# RcMPPT-BMS-Interface.net
KiCad netlist of a schematic drawn in Altium Designer
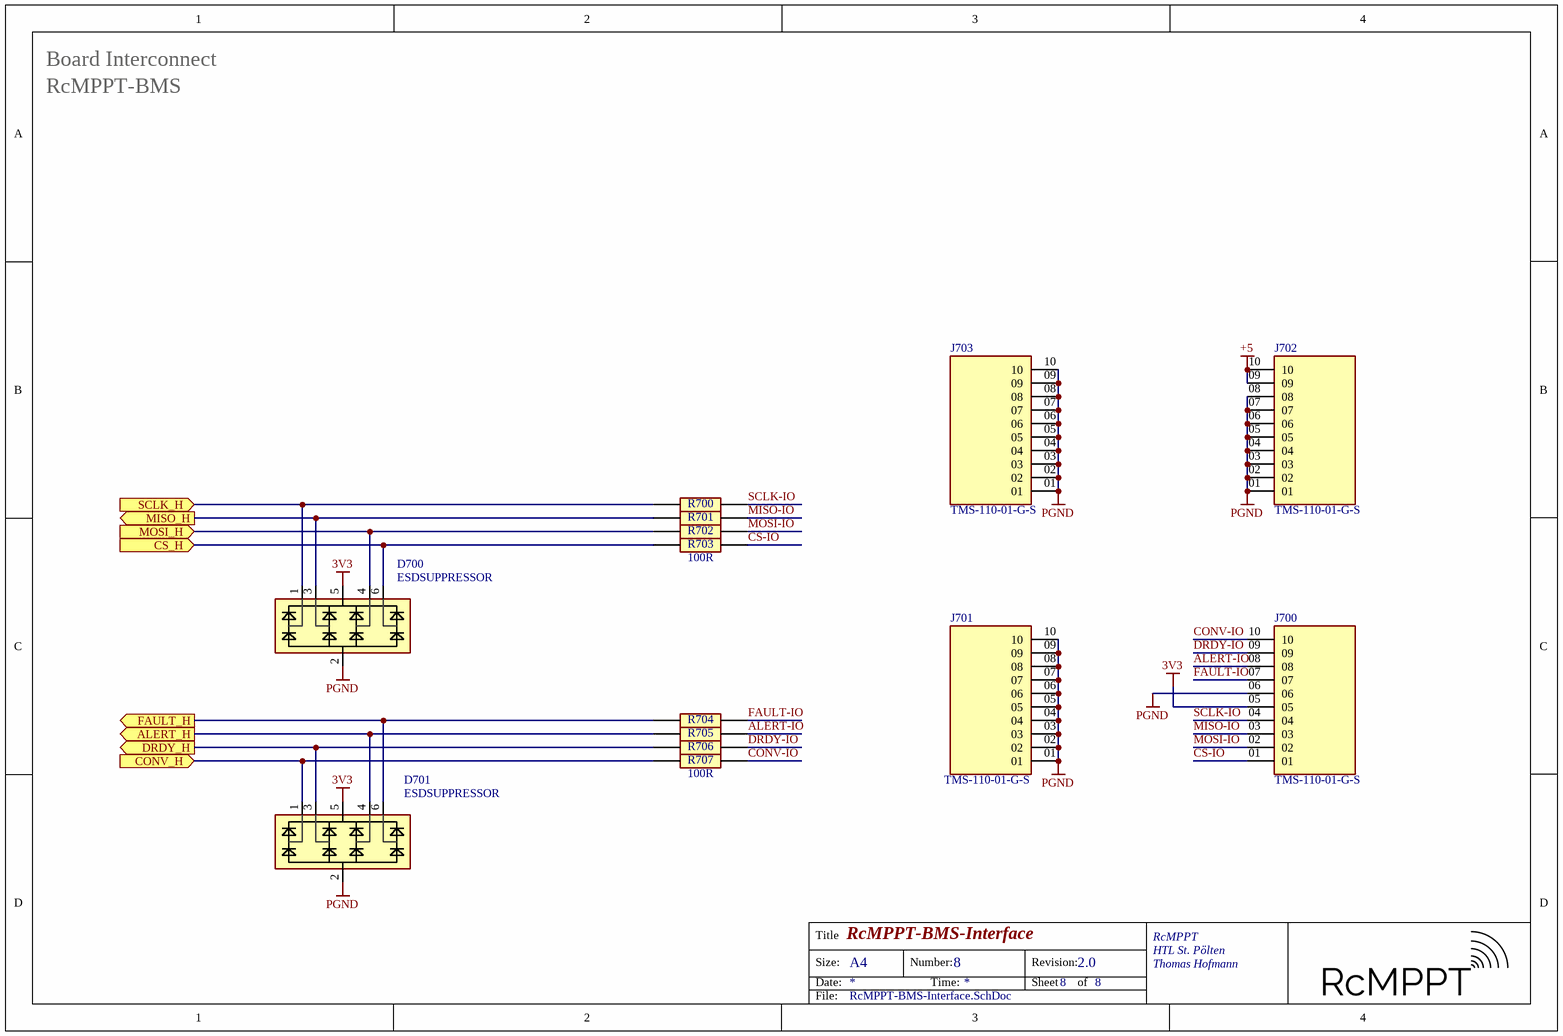
[diagram p0: RcMPPT-BMS-Interface.SchDoc]

(export (version "E")
  (design (tool "Eeschema 10.0.6"))
  (components
    (comp (ref "D700")
      (value "ESDSUPPRESSOR")
      (footprint "SOT23-6")
      (description "TVS Diode Array")
      (libsource (lib "RcMPPTLib") (part "ESDSUPPRESSOR"))
    )
    (comp (ref "D701")
      (value "ESDSUPPRESSOR")
      (footprint "SOT23-6")
      (description "TVS Diode Array")
      (libsource (lib "RcMPPTLib") (part "ESDSUPPRESSOR"))
    )
    (comp (ref "J700")
      (value "TMS-110-01-G-S")
      (footprint "SAMTEC_TMS-110-01-G-S")
      (fields (field (name "MF") "{'manufacturer': u'Samtec'}"))
      (libsource (lib "") (part "TMS-110-01-G-S_1"))
    )
    (comp (ref "J701")
      (value "TMS-110-01-G-S")
      (footprint "SAMTEC_TMS-110-01-G-S")
      (fields (field (name "MF") "{'manufacturer': u'Samtec'}"))
      (libsource (lib "RcMPPTLib") (part "TMS-110-01-G-S"))
    )
    (comp (ref "J702")
      (value "TMS-110-01-G-S")
      (footprint "SAMTEC_TMS-110-01-G-S")
      (fields (field (name "MF") "{'manufacturer': u'Samtec'}"))
      (libsource (lib "") (part "TMS-110-01-G-S_1"))
    )
    (comp (ref "J703")
      (value "TMS-110-01-G-S")
      (footprint "SAMTEC_TMS-110-01-G-S")
      (fields (field (name "MF") "{'manufacturer': u'Samtec'}"))
      (libsource (lib "RcMPPTLib") (part "TMS-110-01-G-S"))
    )
    (comp (ref "R700")
      (value "100R")
      (footprint "RESC1005X40N")
      (description "Resistor")
      (libsource (lib "RcMPPTLib") (part "R0402"))
    )
    (comp (ref "R701")
      (value "100R")
      (footprint "RESC1005X40N")
      (description "Resistor")
      (libsource (lib "RcMPPTLib") (part "R0402"))
    )
    (comp (ref "R702")
      (value "100R")
      (footprint "RESC1005X40N")
      (description "Resistor")
      (libsource (lib "RcMPPTLib") (part "R0402"))
    )
    (comp (ref "R703")
      (value "100R")
      (footprint "RESC1005X40N")
      (description "Resistor")
      (libsource (lib "RcMPPTLib") (part "R0402"))
    )
    (comp (ref "R704")
      (value "100R")
      (footprint "RESC1005X40N")
      (description "Resistor")
      (libsource (lib "RcMPPTLib") (part "R0402"))
    )
    (comp (ref "R705")
      (value "100R")
      (footprint "RESC1005X40N")
      (description "Resistor")
      (libsource (lib "RcMPPTLib") (part "R0402"))
    )
    (comp (ref "R706")
      (value "100R")
      (footprint "RESC1005X40N")
      (description "Resistor")
      (libsource (lib "RcMPPTLib") (part "R0402"))
    )
    (comp (ref "R707")
      (value "100R")
      (footprint "RESC1005X40N")
      (description "Resistor")
      (libsource (lib "RcMPPTLib") (part "R0402"))
    )
  )
  (nets
    (net (code "1") (name "+5") (class "Default")
      (node (ref "J702") (pin "09") (pinfunction "09_09") (pintype "passive"))
      (node (ref "J702") (pin "10") (pinfunction "10_10") (pintype "passive"))
    )
    (net (code "2") (name "/ALERT-IO") (class "Default")
      (node (ref "J700") (pin "08") (pinfunction "08_08") (pintype "passive"))
      (node (ref "R705") (pin "2") (pinfunction "2_2") (pintype "passive"))
    )
    (net (code "3") (name "/ALERT_H") (class "Default")
      (node (ref "D701") (pin "4") (pinfunction "CH3_4") (pintype "passive"))
      (node (ref "R705") (pin "1") (pinfunction "1_1") (pintype "passive"))
    )
    (net (code "4") (name "/CONV-IO") (class "Default")
      (node (ref "J700") (pin "10") (pinfunction "10_10") (pintype "passive"))
      (node (ref "R707") (pin "2") (pinfunction "2_2") (pintype "passive"))
    )
    (net (code "5") (name "/CONV_H") (class "Default")
      (node (ref "D701") (pin "1") (pinfunction "CH1_1") (pintype "passive"))
      (node (ref "R707") (pin "1") (pinfunction "1_1") (pintype "passive"))
    )
    (net (code "6") (name "/CS-IO") (class "Default")
      (node (ref "J700") (pin "01") (pinfunction "01_01") (pintype "passive"))
      (node (ref "R703") (pin "2") (pinfunction "2_2") (pintype "passive"))
    )
    (net (code "7") (name "/CS_H") (class "Default")
      (node (ref "D700") (pin "6") (pinfunction "CH4_6") (pintype "passive"))
      (node (ref "R703") (pin "1") (pinfunction "1_1") (pintype "passive"))
    )
    (net (code "8") (name "/DRDY-IO") (class "Default")
      (node (ref "J700") (pin "09") (pinfunction "09_09") (pintype "passive"))
      (node (ref "R706") (pin "2") (pinfunction "2_2") (pintype "passive"))
    )
    (net (code "9") (name "/DRDY_H") (class "Default")
      (node (ref "D701") (pin "3") (pinfunction "CH2_3") (pintype "passive"))
      (node (ref "R706") (pin "1") (pinfunction "1_1") (pintype "passive"))
    )
    (net (code "10") (name "/FAULT-IO") (class "Default")
      (node (ref "J700") (pin "07") (pinfunction "07_07") (pintype "passive"))
      (node (ref "R704") (pin "2") (pinfunction "2_2") (pintype "passive"))
    )
    (net (code "11") (name "/FAULT_H") (class "Default")
      (node (ref "D701") (pin "6") (pinfunction "CH4_6") (pintype "passive"))
      (node (ref "R704") (pin "1") (pinfunction "1_1") (pintype "passive"))
    )
    (net (code "12") (name "/MISO-IO") (class "Default")
      (node (ref "J700") (pin "03") (pinfunction "03_03") (pintype "passive"))
      (node (ref "R701") (pin "2") (pinfunction "2_2") (pintype "passive"))
    )
    (net (code "13") (name "/MISO_H") (class "Default")
      (node (ref "D700") (pin "3") (pinfunction "CH2_3") (pintype "passive"))
      (node (ref "R701") (pin "1") (pinfunction "1_1") (pintype "passive"))
    )
    (net (code "14") (name "/MOSI-IO") (class "Default")
      (node (ref "J700") (pin "02") (pinfunction "02_02") (pintype "passive"))
      (node (ref "R702") (pin "2") (pinfunction "2_2") (pintype "passive"))
    )
    (net (code "15") (name "/MOSI_H") (class "Default")
      (node (ref "D700") (pin "4") (pinfunction "CH3_4") (pintype "passive"))
      (node (ref "R702") (pin "1") (pinfunction "1_1") (pintype "passive"))
    )
    (net (code "16") (name "/SCLK-IO") (class "Default")
      (node (ref "J700") (pin "04") (pinfunction "04_04") (pintype "passive"))
      (node (ref "R700") (pin "2") (pinfunction "2_2") (pintype "passive"))
    )
    (net (code "17") (name "/SCLK_H") (class "Default")
      (node (ref "D700") (pin "1") (pinfunction "CH1_1") (pintype "passive"))
      (node (ref "R700") (pin "1") (pinfunction "1_1") (pintype "passive"))
    )
    (net (code "18") (name "3V3") (class "Default")
      (node (ref "D700") (pin "5") (pinfunction "VDD_5") (pintype "passive"))
      (node (ref "D701") (pin "5") (pinfunction "VDD_5") (pintype "passive"))
      (node (ref "J700") (pin "05") (pinfunction "05_05") (pintype "passive"))
    )
    (net (code "19") (name "PGND") (class "Default")
      (node (ref "D700") (pin "2") (pinfunction "GND_2") (pintype "passive"))
      (node (ref "D701") (pin "2") (pinfunction "GND_2") (pintype "passive"))
      (node (ref "J700") (pin "06") (pinfunction "06_06") (pintype "passive"))
      (node (ref "J701") (pin "01") (pinfunction "01_01") (pintype "passive"))
      (node (ref "J701") (pin "02") (pinfunction "02_02") (pintype "passive"))
      (node (ref "J701") (pin "03") (pinfunction "03_03") (pintype "passive"))
      (node (ref "J701") (pin "04") (pinfunction "04_04") (pintype "passive"))
      (node (ref "J701") (pin "05") (pinfunction "05_05") (pintype "passive"))
      (node (ref "J701") (pin "06") (pinfunction "06_06") (pintype "passive"))
      (node (ref "J701") (pin "07") (pinfunction "07_07") (pintype "passive"))
      (node (ref "J701") (pin "08") (pinfunction "08_08") (pintype "passive"))
      (node (ref "J701") (pin "09") (pinfunction "09_09") (pintype "passive"))
      (node (ref "J701") (pin "10") (pinfunction "10_10") (pintype "passive"))
      (node (ref "J702") (pin "01") (pinfunction "01_01") (pintype "passive"))
      (node (ref "J702") (pin "02") (pinfunction "02_02") (pintype "passive"))
      (node (ref "J702") (pin "03") (pinfunction "03_03") (pintype "passive"))
      (node (ref "J702") (pin "04") (pinfunction "04_04") (pintype "passive"))
      (node (ref "J702") (pin "05") (pinfunction "05_05") (pintype "passive"))
      (node (ref "J702") (pin "06") (pinfunction "06_06") (pintype "passive"))
      (node (ref "J702") (pin "07") (pinfunction "07_07") (pintype "passive"))
      (node (ref "J702") (pin "08") (pinfunction "08_08") (pintype "passive"))
      (node (ref "J703") (pin "01") (pinfunction "01_01") (pintype "passive"))
      (node (ref "J703") (pin "02") (pinfunction "02_02") (pintype "passive"))
      (node (ref "J703") (pin "03") (pinfunction "03_03") (pintype "passive"))
      (node (ref "J703") (pin "04") (pinfunction "04_04") (pintype "passive"))
      (node (ref "J703") (pin "05") (pinfunction "05_05") (pintype "passive"))
      (node (ref "J703") (pin "06") (pinfunction "06_06") (pintype "passive"))
      (node (ref "J703") (pin "07") (pinfunction "07_07") (pintype "passive"))
      (node (ref "J703") (pin "08") (pinfunction "08_08") (pintype "passive"))
      (node (ref "J703") (pin "09") (pinfunction "09_09") (pintype "passive"))
      (node (ref "J703") (pin "10") (pinfunction "10_10") (pintype "passive"))
    )
  )
)
